# tx-audio_breakout.net
KiCad netlist of a schematic drawn in EAGLE
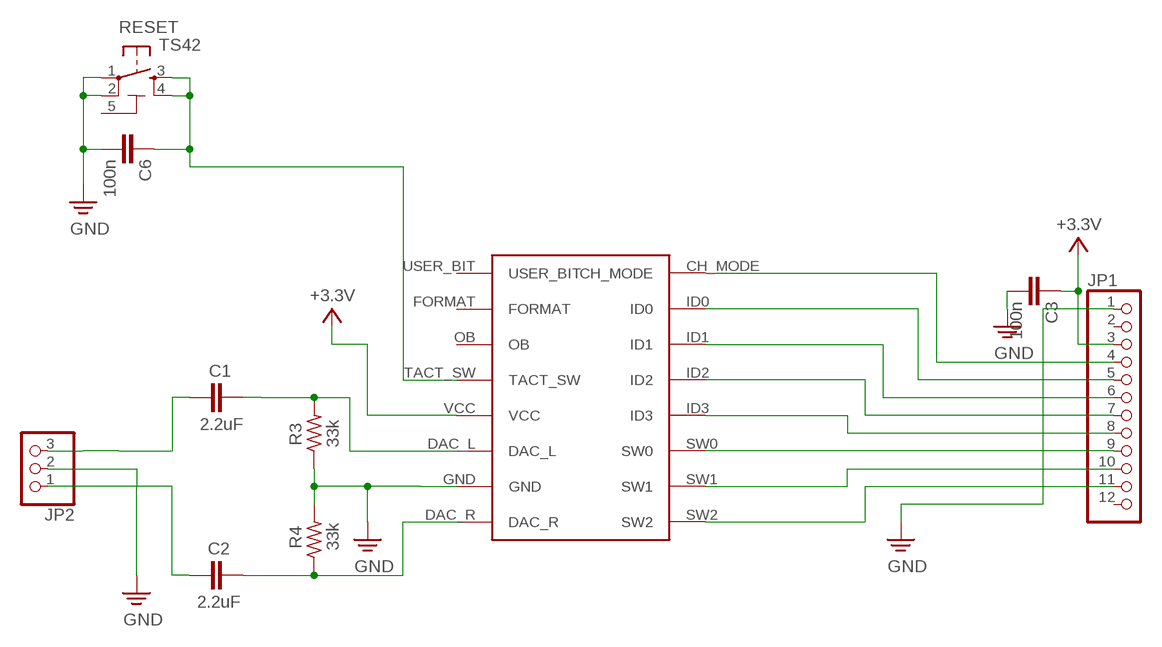
[diagram p0: schematic, sheet 1]

(export (version "E")
  (design (tool "Eeschema 10.0.6"))
  (components
    (comp (ref "C1")
      (value "2.2uF")
      (footprint "eagle-import:0805A")
      (libsource (lib "eagle-import") (part "CAPACITOR0805"))
    )
    (comp (ref "C2")
      (value "2.2uF")
      (footprint "eagle-import:0805A")
      (libsource (lib "eagle-import") (part "CAPACITOR0805"))
    )
    (comp (ref "C3")
      (value "100n")
      (footprint "eagle-import:C0805")
      (libsource (lib "eagle-import") (part "C-EUC0805"))
    )
    (comp (ref "C6")
      (value "100n")
      (footprint "eagle-import:C0805")
      (libsource (lib "eagle-import") (part "C-EUC0805"))
    )
    (comp (ref "JP1")
      (value "PINHD-1X12")
      (footprint "eagle-import:1X12")
      (libsource (lib "eagle-import") (part "PINHD-1X12"))
    )
    (comp (ref "JP2")
      (value "PINHD-1X3")
      (footprint "eagle-import:1X03")
      (libsource (lib "eagle-import") (part "PINHD-1X3"))
    )
    (comp (ref "R3")
      (value "33k")
      (footprint "eagle-import:0805A")
      (libsource (lib "eagle-import") (part "RESISTOR0805"))
    )
    (comp (ref "R4")
      (value "33k")
      (footprint "eagle-import:0805A")
      (libsource (lib "eagle-import") (part "RESISTOR0805"))
    )
    (comp (ref "RESET")
      (value "TS42")
      (footprint "eagle-import:TS42")
      (libsource (lib "eagle-import") (part "TS42"))
    )
    (comp (ref "U$1")
      (value "TX-AUDIO-2.4VERTICAL")
      (footprint "eagle-import:AUREL-TX-AUDIO-2.4GH-TRH")
      (libsource (lib "eagle-import") (part "TX-AUDIO-2.4VERTICAL"))
    )
  )
  (nets
    (net (code "1") (name "+3.3V") (class "Default")
      (node (ref "C3") (pin "1") (pinfunction "1_1") (pintype "passive"))
      (node (ref "JP1") (pin "3") (pinfunction "3_3") (pintype "passive"))
      (node (ref "U$1") (pin "VCC") (pinfunction "VCC_VCC") (pintype "bidirectional"))
    )
    (net (code "2") (name "/5-GND") (class "Default")
      (node (ref "RESET") (pin "5") (pinfunction "5-GND_5") (pintype "power_in"))
    )
    (net (code "3") (name "GND") (class "Default")
      (node (ref "C3") (pin "2") (pinfunction "2_2") (pintype "passive"))
      (node (ref "C6") (pin "2") (pinfunction "2_2") (pintype "passive"))
      (node (ref "JP1") (pin "1") (pinfunction "1_1") (pintype "passive"))
      (node (ref "JP2") (pin "2") (pinfunction "2_2") (pintype "passive"))
      (node (ref "R3") (pin "+") (pinfunction "1_+") (pintype "passive"))
      (node (ref "R4") (pin "-") (pinfunction "2_-") (pintype "passive"))
      (node (ref "RESET") (pin "1") (pinfunction "1_1") (pintype "passive"))
      (node (ref "RESET") (pin "2") (pinfunction "2_2") (pintype "passive"))
      (node (ref "U$1") (pin "GND") (pinfunction "GND_GND") (pintype "bidirectional"))
    )
    (net (code "4") (name "Net-(C1-1)") (class "Default")
      (node (ref "C1") (pin "+") (pinfunction "1_+") (pintype "passive"))
      (node (ref "JP2") (pin "3") (pinfunction "3_3") (pintype "passive"))
    )
    (net (code "5") (name "Net-(C1-2)") (class "Default")
      (node (ref "C1") (pin "-") (pinfunction "2_-") (pintype "passive"))
      (node (ref "R3") (pin "-") (pinfunction "2_-") (pintype "passive"))
      (node (ref "U$1") (pin "DAC_L") (pinfunction "DAC_L_DAC_L") (pintype "bidirectional"))
    )
    (net (code "6") (name "Net-(C2-1)") (class "Default")
      (node (ref "C2") (pin "+") (pinfunction "1_+") (pintype "passive"))
      (node (ref "R4") (pin "+") (pinfunction "1_+") (pintype "passive"))
      (node (ref "U$1") (pin "DAC_R") (pinfunction "DAC_R_DAC_R") (pintype "bidirectional"))
    )
    (net (code "7") (name "Net-(C2-2)") (class "Default")
      (node (ref "C2") (pin "-") (pinfunction "2_-") (pintype "passive"))
      (node (ref "JP2") (pin "1") (pinfunction "1_1") (pintype "passive"))
    )
    (net (code "8") (name "Net-(C6-Pad1)") (class "Default")
      (node (ref "C6") (pin "1") (pinfunction "1_1") (pintype "passive"))
      (node (ref "RESET") (pin "3") (pinfunction "3_3") (pintype "passive"))
      (node (ref "RESET") (pin "4") (pinfunction "4_4") (pintype "passive"))
      (node (ref "U$1") (pin "TACT_SW") (pinfunction "TACT_SW_TACT_SW") (pintype "bidirectional"))
    )
    (net (code "9") (name "Net-(JP1-Pad4)") (class "Default")
      (node (ref "JP1") (pin "4") (pinfunction "4_4") (pintype "passive"))
      (node (ref "U$1") (pin "CH_MODE") (pinfunction "CH_MODE_CH_MODE") (pintype "bidirectional"))
    )
    (net (code "10") (name "Net-(JP1-Pad5)") (class "Default")
      (node (ref "JP1") (pin "5") (pinfunction "5_5") (pintype "passive"))
      (node (ref "U$1") (pin "ID0") (pinfunction "ID0_ID0") (pintype "bidirectional"))
    )
    (net (code "11") (name "Net-(JP1-Pad6)") (class "Default")
      (node (ref "JP1") (pin "6") (pinfunction "6_6") (pintype "passive"))
      (node (ref "U$1") (pin "ID1") (pinfunction "ID1_ID1") (pintype "bidirectional"))
    )
    (net (code "12") (name "Net-(JP1-Pad7)") (class "Default")
      (node (ref "JP1") (pin "7") (pinfunction "7_7") (pintype "passive"))
      (node (ref "U$1") (pin "ID2") (pinfunction "ID2_ID2") (pintype "bidirectional"))
    )
    (net (code "13") (name "Net-(JP1-Pad8)") (class "Default")
      (node (ref "JP1") (pin "8") (pinfunction "8_8") (pintype "passive"))
      (node (ref "U$1") (pin "ID3") (pinfunction "ID3_ID3") (pintype "bidirectional"))
    )
    (net (code "14") (name "Net-(JP1-Pad9)") (class "Default")
      (node (ref "JP1") (pin "9") (pinfunction "9_9") (pintype "passive"))
      (node (ref "U$1") (pin "SW0") (pinfunction "SW0_SW0") (pintype "bidirectional"))
    )
    (net (code "15") (name "Net-(JP1-Pad10)") (class "Default")
      (node (ref "JP1") (pin "10") (pinfunction "10_10") (pintype "passive"))
      (node (ref "U$1") (pin "SW1") (pinfunction "SW1_SW1") (pintype "bidirectional"))
    )
    (net (code "16") (name "Net-(JP1-Pad11)") (class "Default")
      (node (ref "JP1") (pin "11") (pinfunction "11_11") (pintype "passive"))
      (node (ref "U$1") (pin "SW2") (pinfunction "SW2_SW2") (pintype "bidirectional"))
    )
    (net (code "17") (name "unconnected-(JP1-Pad2)") (class "Default")
      (node (ref "JP1") (pin "2") (pinfunction "2_2") (pintype "passive"))
    )
    (net (code "18") (name "unconnected-(JP1-Pad12)") (class "Default")
      (node (ref "JP1") (pin "12") (pinfunction "12_12") (pintype "passive"))
    )
    (net (code "19") (name "unconnected-(U$1-PadFORMAT)") (class "Default")
      (node (ref "U$1") (pin "FORMAT") (pinfunction "FORMAT_FORMAT") (pintype "bidirectional"))
    )
    (net (code "20") (name "unconnected-(U$1-PadOB)") (class "Default")
      (node (ref "U$1") (pin "OB") (pinfunction "OB_OB") (pintype "bidirectional"))
    )
    (net (code "21") (name "unconnected-(U$1-PadUSER_BIT)") (class "Default")
      (node (ref "U$1") (pin "USER_BIT") (pinfunction "USER_BIT_USER_BIT") (pintype "bidirectional"))
    )
  )
)
